# Sheet2.net
KiCad netlist of a schematic drawn in Altium Designer
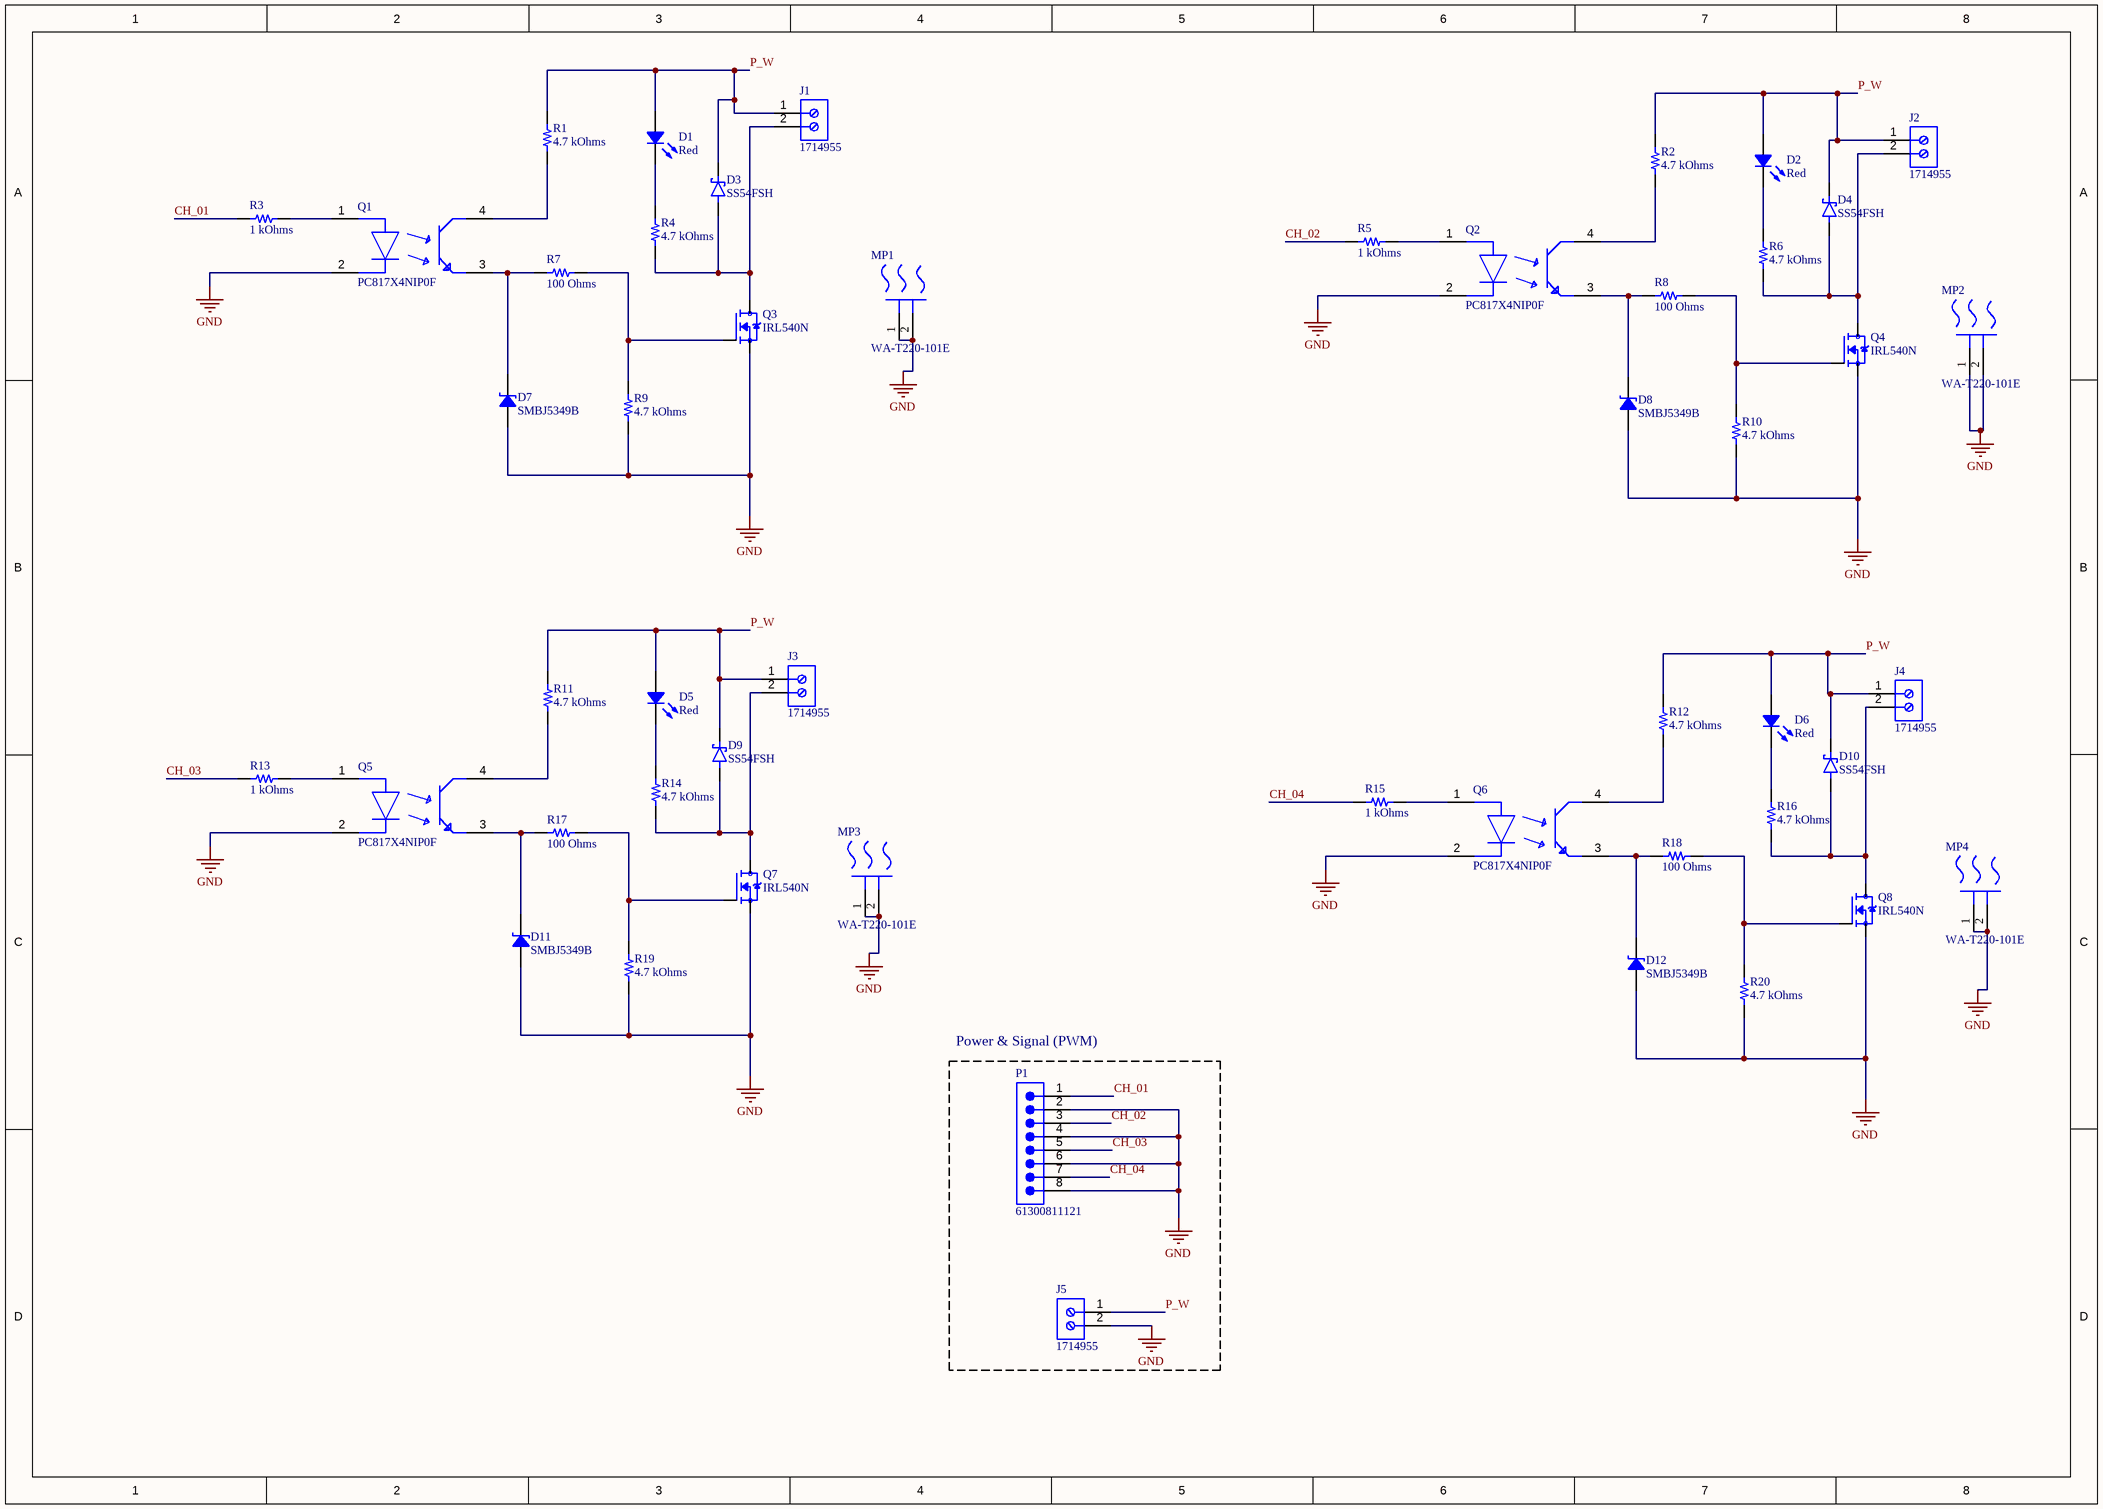
[diagram p0: Sheet2.SchDoc]

(export (version "E")
  (design (tool "Eeschema 10.0.6"))
  (components
    (comp (ref "D1")
      (value "Red")
      (footprint "LED 0603_1608 RED")
      (description "LED RED 0603 SMD")
      (fields (field (name "PART NUMBER") "5973005507F") (field (name "MANUFACTURER") "Dialight"))
      (libsource (lib "Celestial Altium Library - altium_library") (part "LED"))
    )
    (comp (ref "D2")
      (value "Red")
      (footprint "LED 0603_1608 RED")
      (description "LED RED 0603 SMD")
      (fields (field (name "PART NUMBER") "5973005507F") (field (name "MANUFACTURER") "Dialight"))
      (libsource (lib "Celestial Altium Library - altium_library") (part "LED"))
    )
    (comp (ref "D3")
      (value "SS54FSH")
      (footprint "SODFL4725X110N")
      (description "5A, 40V, Schottky Rectifier")
      (fields (field (name "MF") "Taiwan Semiconductor"))
      (libsource (lib "SS54FSH") (part "SS54FSH"))
    )
    (comp (ref "D4")
      (value "SS54FSH")
      (footprint "SODFL4725X110N")
      (description "5A, 40V, Schottky Rectifier")
      (fields (field (name "MF") "Taiwan Semiconductor"))
      (libsource (lib "SS54FSH") (part "SS54FSH"))
    )
    (comp (ref "D5")
      (value "Red")
      (footprint "LED 0603_1608 RED")
      (description "LED RED 0603 SMD")
      (fields (field (name "PART NUMBER") "5973005507F") (field (name "MANUFACTURER") "Dialight"))
      (libsource (lib "Celestial Altium Library - altium_library") (part "LED"))
    )
    (comp (ref "D6")
      (value "Red")
      (footprint "LED 0603_1608 RED")
      (description "LED RED 0603 SMD")
      (fields (field (name "PART NUMBER") "5973005507F") (field (name "MANUFACTURER") "Dialight"))
      (libsource (lib "Celestial Altium Library - altium_library") (part "LED"))
    )
    (comp (ref "D7")
      (value "SMBJ5349B")
      (footprint "DO214AA SMB")
      (description "DIODE ZENER 12V 5W DO214AA")
      (fields (field (name "PART NUMBER") "SMBJ5349B-TP") (field (name "MANUFACTURER") "Micro Commercial Co"))
      (libsource (lib "Celestial Altium Library - altium_library") (part "Diode Zener"))
    )
    (comp (ref "D8")
      (value "SMBJ5349B")
      (footprint "DO214AA SMB")
      (description "DIODE ZENER 12V 5W DO214AA")
      (fields (field (name "PART NUMBER") "SMBJ5349B-TP") (field (name "MANUFACTURER") "Micro Commercial Co"))
      (libsource (lib "Celestial Altium Library - altium_library") (part "Diode Zener"))
    )
    (comp (ref "D9")
      (value "SS54FSH")
      (footprint "SODFL4725X110N")
      (description "5A, 40V, Schottky Rectifier")
      (fields (field (name "MF") "Taiwan Semiconductor"))
      (libsource (lib "SS54FSH") (part "SS54FSH"))
    )
    (comp (ref "D10")
      (value "SS54FSH")
      (footprint "SODFL4725X110N")
      (description "5A, 40V, Schottky Rectifier")
      (fields (field (name "MF") "Taiwan Semiconductor"))
      (libsource (lib "SS54FSH") (part "SS54FSH"))
    )
    (comp (ref "D11")
      (value "SMBJ5349B")
      (footprint "DO214AA SMB")
      (description "DIODE ZENER 12V 5W DO214AA")
      (fields (field (name "PART NUMBER") "SMBJ5349B-TP") (field (name "MANUFACTURER") "Micro Commercial Co"))
      (libsource (lib "Celestial Altium Library - altium_library") (part "Diode Zener"))
    )
    (comp (ref "D12")
      (value "SMBJ5349B")
      (footprint "DO214AA SMB")
      (description "DIODE ZENER 12V 5W DO214AA")
      (fields (field (name "PART NUMBER") "SMBJ5349B-TP") (field (name "MANUFACTURER") "Micro Commercial Co"))
      (libsource (lib "Celestial Altium Library - altium_library") (part "Diode Zener"))
    )
    (comp (ref "J1")
      (value "1714955")
      (footprint "PHOE-1714955_V")
      (description "PC Terminal Block, Pitch 6.35 mm, 1 x 2 Position, Height 21.5 mm, Tail Lenght 5.1 mm, RoHS, Bulk")
      (fields (field (name "MANUFACTURER") "Phoenix Contact"))
      (libsource (lib "Altium Content Vault") (part "CN-1P-F-TB2"))
    )
    (comp (ref "J2")
      (value "1714955")
      (footprint "PHOE-1714955_V")
      (description "PC Terminal Block, Pitch 6.35 mm, 1 x 2 Position, Height 21.5 mm, Tail Lenght 5.1 mm, RoHS, Bulk")
      (fields (field (name "MANUFACTURER") "Phoenix Contact"))
      (libsource (lib "Altium Content Vault") (part "CN-1P-F-TB2"))
    )
    (comp (ref "J3")
      (value "1714955")
      (footprint "PHOE-1714955_V")
      (description "PC Terminal Block, Pitch 6.35 mm, 1 x 2 Position, Height 21.5 mm, Tail Lenght 5.1 mm, RoHS, Bulk")
      (fields (field (name "MANUFACTURER") "Phoenix Contact"))
      (libsource (lib "Altium Content Vault") (part "CN-1P-F-TB2"))
    )
    (comp (ref "J4")
      (value "1714955")
      (footprint "PHOE-1714955_V")
      (description "PC Terminal Block, Pitch 6.35 mm, 1 x 2 Position, Height 21.5 mm, Tail Lenght 5.1 mm, RoHS, Bulk")
      (fields (field (name "MANUFACTURER") "Phoenix Contact"))
      (libsource (lib "Altium Content Vault") (part "CN-1P-F-TB2"))
    )
    (comp (ref "J5")
      (value "1714955")
      (footprint "PHOE-1714955_V")
      (description "PC Terminal Block, Pitch 6.35 mm, 1 x 2 Position, Height 21.5 mm, Tail Lenght 5.1 mm, RoHS, Bulk")
      (fields (field (name "MANUFACTURER") "Phoenix Contact"))
      (libsource (lib "Altium Content Vault") (part "CN-1P-F-TB2"))
    )
    (comp (ref "MP1")
      (value "WA-T220-101E")
      (footprint "FP-WA-T220-101E-MFG")
      (description "HEATSINK AND CLIP FOR TO-220 BLK")
      (libsource (lib "Altium Content Vault") (part "1c0b9ce64b05bcdbb02c4237765ddae"))
    )
    (comp (ref "MP2")
      (value "WA-T220-101E")
      (footprint "FP-WA-T220-101E-MFG")
      (description "HEATSINK AND CLIP FOR TO-220 BLK")
      (libsource (lib "Altium Content Vault") (part "1c0b9ce64b05bcdbb02c4237765ddae"))
    )
    (comp (ref "MP3")
      (value "WA-T220-101E")
      (footprint "FP-WA-T220-101E-MFG")
      (description "HEATSINK AND CLIP FOR TO-220 BLK")
      (libsource (lib "Altium Content Vault") (part "1c0b9ce64b05bcdbb02c4237765ddae"))
    )
    (comp (ref "MP4")
      (value "WA-T220-101E")
      (footprint "FP-WA-T220-101E-MFG")
      (description "HEATSINK AND CLIP FOR TO-220 BLK")
      (libsource (lib "Altium Content Vault") (part "1c0b9ce64b05bcdbb02c4237765ddae"))
    )
    (comp (ref "P1")
      (value "61300811121")
      (footprint "61300811121")
      (libsource (lib "Altium Content Vault") (part "Header_Male_1R_08P"))
    )
    (comp (ref "Q1")
      (value "PC817X4NIP0F")
      (footprint "FP-PC817X4NIP0F-MFG")
      (description "OPTOISOLATOR 5KV TRANS 4SMD")
      (fields
        (field (name "OCTOPART") "https://octopart.com/pc817x4nip0f-sharp-20650453")
        (field (name "MANUFACTURER") "Sharp")
      )
      (libsource (lib "Altium Content Vault") (part "8ff5844b63c0dea0057760e9ee25456"))
    )
    (comp (ref "Q2")
      (value "PC817X4NIP0F")
      (footprint "FP-PC817X4NIP0F-MFG")
      (description "OPTOISOLATOR 5KV TRANS 4SMD")
      (fields
        (field (name "OCTOPART") "https://octopart.com/pc817x4nip0f-sharp-20650453")
        (field (name "MANUFACTURER") "Sharp")
      )
      (libsource (lib "Altium Content Vault") (part "8ff5844b63c0dea0057760e9ee25456"))
    )
    (comp (ref "Q3")
      (value "IRL540N")
      (footprint "TO254P1054X469X1930-3")
      (fields (field (name "MP") "IRF540NPBF") (field (name "MF") "Infineon"))
      (libsource (lib "IRF540NPBF") (part "IRF540NPBF"))
    )
    (comp (ref "Q4")
      (value "IRL540N")
      (footprint "TO254P1054X469X1930-3")
      (fields (field (name "MP") "IRF540NPBF") (field (name "MF") "Infineon"))
      (libsource (lib "IRF540NPBF") (part "IRF540NPBF"))
    )
    (comp (ref "Q5")
      (value "PC817X4NIP0F")
      (footprint "FP-PC817X4NIP0F-MFG")
      (description "OPTOISOLATOR 5KV TRANS 4SMD")
      (fields
        (field (name "OCTOPART") "https://octopart.com/pc817x4nip0f-sharp-20650453")
        (field (name "MANUFACTURER") "Sharp")
      )
      (libsource (lib "Altium Content Vault") (part "8ff5844b63c0dea0057760e9ee25456"))
    )
    (comp (ref "Q6")
      (value "PC817X4NIP0F")
      (footprint "FP-PC817X4NIP0F-MFG")
      (description "OPTOISOLATOR 5KV TRANS 4SMD")
      (fields
        (field (name "OCTOPART") "https://octopart.com/pc817x4nip0f-sharp-20650453")
        (field (name "MANUFACTURER") "Sharp")
      )
      (libsource (lib "Altium Content Vault") (part "8ff5844b63c0dea0057760e9ee25456"))
    )
    (comp (ref "Q7")
      (value "IRL540N")
      (footprint "TO254P1054X469X1930-3")
      (fields (field (name "MP") "IRF540NPBF") (field (name "MF") "Infineon"))
      (libsource (lib "IRF540NPBF") (part "IRF540NPBF"))
    )
    (comp (ref "Q8")
      (value "IRL540N")
      (footprint "TO254P1054X469X1930-3")
      (fields (field (name "MP") "IRF540NPBF") (field (name "MF") "Infineon"))
      (libsource (lib "IRF540NPBF") (part "IRF540NPBF"))
    )
    (comp (ref "R1")
      (value "4.7 kOhms")
      (footprint "RES 0603_1608")
      (description "RES SMD 4.7K OHM 0.1% 1/10W 0603")
      (fields
        (field (name "PART NUMBER") "ERA-3AEB472V")
        (field (name "MANUFACTURER") "Panasonic Electronic Components")
      )
      (libsource (lib "Celestial Altium Library - altium_library") (part "Resistor"))
    )
    (comp (ref "R2")
      (value "4.7 kOhms")
      (footprint "RES 0603_1608")
      (description "RES SMD 4.7K OHM 0.1% 1/10W 0603")
      (fields
        (field (name "PART NUMBER") "ERA-3AEB472V")
        (field (name "MANUFACTURER") "Panasonic Electronic Components")
      )
      (libsource (lib "Celestial Altium Library - altium_library") (part "Resistor"))
    )
    (comp (ref "R3")
      (value "1 kOhms")
      (footprint "RES 0603_1608")
      (description "RES SMD 1K OHM 0.1% 1/16W 0603")
      (fields
        (field (name "PART NUMBER") "CPF0603B1K0E")
        (field (name "MANUFACTURER") "TE Connectivity Passive Product")
      )
      (libsource (lib "Celestial Altium Library - altium_library") (part "Resistor"))
    )
    (comp (ref "R4")
      (value "4.7 kOhms")
      (footprint "RES 0603_1608")
      (description "RES SMD 4.7K OHM 0.1% 1/10W 0603")
      (fields
        (field (name "PART NUMBER") "ERA-3AEB472V")
        (field (name "MANUFACTURER") "Panasonic Electronic Components")
      )
      (libsource (lib "Celestial Altium Library - altium_library") (part "Resistor"))
    )
    (comp (ref "R5")
      (value "1 kOhms")
      (footprint "RES 0603_1608")
      (description "RES SMD 1K OHM 0.1% 1/16W 0603")
      (fields
        (field (name "PART NUMBER") "CPF0603B1K0E")
        (field (name "MANUFACTURER") "TE Connectivity Passive Product")
      )
      (libsource (lib "Celestial Altium Library - altium_library") (part "Resistor"))
    )
    (comp (ref "R6")
      (value "4.7 kOhms")
      (footprint "RES 0603_1608")
      (description "RES SMD 4.7K OHM 0.1% 1/10W 0603")
      (fields
        (field (name "PART NUMBER") "ERA-3AEB472V")
        (field (name "MANUFACTURER") "Panasonic Electronic Components")
      )
      (libsource (lib "Celestial Altium Library - altium_library") (part "Resistor"))
    )
    (comp (ref "R7")
      (value "100 Ohms")
      (footprint "RES 0603_1608")
      (description "RES 100 OHM 0.1% 1/16W 0603")
      (fields
        (field (name "PART NUMBER") "RNCS0603BKE100R")
        (field (name "MANUFACTURER") "Stackpole Electronics Inc")
      )
      (libsource (lib "Celestial Altium Library - altium_library") (part "Resistor"))
    )
    (comp (ref "R8")
      (value "100 Ohms")
      (footprint "RES 0603_1608")
      (description "RES 100 OHM 0.1% 1/16W 0603")
      (fields
        (field (name "PART NUMBER") "RNCS0603BKE100R")
        (field (name "MANUFACTURER") "Stackpole Electronics Inc")
      )
      (libsource (lib "Celestial Altium Library - altium_library") (part "Resistor"))
    )
    (comp (ref "R9")
      (value "4.7 kOhms")
      (footprint "RES 0603_1608")
      (description "RES SMD 4.7K OHM 0.1% 1/10W 0603")
      (fields
        (field (name "PART NUMBER") "ERA-3AEB472V")
        (field (name "MANUFACTURER") "Panasonic Electronic Components")
      )
      (libsource (lib "Celestial Altium Library - altium_library") (part "Resistor"))
    )
    (comp (ref "R10")
      (value "4.7 kOhms")
      (footprint "RES 0603_1608")
      (description "RES SMD 4.7K OHM 0.1% 1/10W 0603")
      (fields
        (field (name "PART NUMBER") "ERA-3AEB472V")
        (field (name "MANUFACTURER") "Panasonic Electronic Components")
      )
      (libsource (lib "Celestial Altium Library - altium_library") (part "Resistor"))
    )
    (comp (ref "R11")
      (value "4.7 kOhms")
      (footprint "RES 0603_1608")
      (description "RES SMD 4.7K OHM 0.1% 1/10W 0603")
      (fields
        (field (name "PART NUMBER") "ERA-3AEB472V")
        (field (name "MANUFACTURER") "Panasonic Electronic Components")
      )
      (libsource (lib "Celestial Altium Library - altium_library") (part "Resistor"))
    )
    (comp (ref "R12")
      (value "4.7 kOhms")
      (footprint "RES 0603_1608")
      (description "RES SMD 4.7K OHM 0.1% 1/10W 0603")
      (fields
        (field (name "PART NUMBER") "ERA-3AEB472V")
        (field (name "MANUFACTURER") "Panasonic Electronic Components")
      )
      (libsource (lib "Celestial Altium Library - altium_library") (part "Resistor"))
    )
    (comp (ref "R13")
      (value "1 kOhms")
      (footprint "RES 0603_1608")
      (description "RES SMD 1K OHM 0.1% 1/16W 0603")
      (fields
        (field (name "PART NUMBER") "CPF0603B1K0E")
        (field (name "MANUFACTURER") "TE Connectivity Passive Product")
      )
      (libsource (lib "Celestial Altium Library - altium_library") (part "Resistor"))
    )
    (comp (ref "R14")
      (value "4.7 kOhms")
      (footprint "RES 0603_1608")
      (description "RES SMD 4.7K OHM 0.1% 1/10W 0603")
      (fields
        (field (name "PART NUMBER") "ERA-3AEB472V")
        (field (name "MANUFACTURER") "Panasonic Electronic Components")
      )
      (libsource (lib "Celestial Altium Library - altium_library") (part "Resistor"))
    )
    (comp (ref "R15")
      (value "1 kOhms")
      (footprint "RES 0603_1608")
      (description "RES SMD 1K OHM 0.1% 1/16W 0603")
      (fields
        (field (name "PART NUMBER") "CPF0603B1K0E")
        (field (name "MANUFACTURER") "TE Connectivity Passive Product")
      )
      (libsource (lib "Celestial Altium Library - altium_library") (part "Resistor"))
    )
    (comp (ref "R16")
      (value "4.7 kOhms")
      (footprint "RES 0603_1608")
      (description "RES SMD 4.7K OHM 0.1% 1/10W 0603")
      (fields
        (field (name "PART NUMBER") "ERA-3AEB472V")
        (field (name "MANUFACTURER") "Panasonic Electronic Components")
      )
      (libsource (lib "Celestial Altium Library - altium_library") (part "Resistor"))
    )
    (comp (ref "R17")
      (value "100 Ohms")
      (footprint "RES 0603_1608")
      (description "RES 100 OHM 0.1% 1/16W 0603")
      (fields
        (field (name "PART NUMBER") "RNCS0603BKE100R")
        (field (name "MANUFACTURER") "Stackpole Electronics Inc")
      )
      (libsource (lib "Celestial Altium Library - altium_library") (part "Resistor"))
    )
    (comp (ref "R18")
      (value "100 Ohms")
      (footprint "RES 0603_1608")
      (description "RES 100 OHM 0.1% 1/16W 0603")
      (fields
        (field (name "PART NUMBER") "RNCS0603BKE100R")
        (field (name "MANUFACTURER") "Stackpole Electronics Inc")
      )
      (libsource (lib "Celestial Altium Library - altium_library") (part "Resistor"))
    )
    (comp (ref "R19")
      (value "4.7 kOhms")
      (footprint "RES 0603_1608")
      (description "RES SMD 4.7K OHM 0.1% 1/10W 0603")
      (fields
        (field (name "PART NUMBER") "ERA-3AEB472V")
        (field (name "MANUFACTURER") "Panasonic Electronic Components")
      )
      (libsource (lib "Celestial Altium Library - altium_library") (part "Resistor"))
    )
    (comp (ref "R20")
      (value "4.7 kOhms")
      (footprint "RES 0603_1608")
      (description "RES SMD 4.7K OHM 0.1% 1/10W 0603")
      (fields
        (field (name "PART NUMBER") "ERA-3AEB472V")
        (field (name "MANUFACTURER") "Panasonic Electronic Components")
      )
      (libsource (lib "Celestial Altium Library - altium_library") (part "Resistor"))
    )
  )
  (nets
    (net (code "1") (name "/CH_01") (class "Default")
      (node (ref "P1") (pin "1") (pinfunction "1_1") (pintype "passive"))
      (node (ref "R3") (pin "1") (pinfunction "1_1") (pintype "passive"))
    )
    (net (code "2") (name "/CH_02") (class "Default")
      (node (ref "P1") (pin "3") (pinfunction "3_3") (pintype "passive"))
      (node (ref "R5") (pin "1") (pinfunction "1_1") (pintype "passive"))
    )
    (net (code "3") (name "/CH_03") (class "Default")
      (node (ref "P1") (pin "5") (pinfunction "5_5") (pintype "passive"))
      (node (ref "R13") (pin "1") (pinfunction "1_1") (pintype "passive"))
    )
    (net (code "4") (name "/CH_04") (class "Default")
      (node (ref "P1") (pin "7") (pinfunction "7_7") (pintype "passive"))
      (node (ref "R15") (pin "1") (pinfunction "1_1") (pintype "passive"))
    )
    (net (code "5") (name "/P_W") (class "Default")
      (node (ref "D1") (pin "1") (pinfunction "1_1") (pintype "passive"))
      (node (ref "D10") (pin "C") (pinfunction "K_C") (pintype "passive"))
      (node (ref "D2") (pin "1") (pinfunction "1_1") (pintype "passive"))
      (node (ref "D3") (pin "C") (pinfunction "K_C") (pintype "passive"))
      (node (ref "D4") (pin "C") (pinfunction "K_C") (pintype "passive"))
      (node (ref "D5") (pin "1") (pinfunction "1_1") (pintype "passive"))
      (node (ref "D6") (pin "1") (pinfunction "1_1") (pintype "passive"))
      (node (ref "D9") (pin "C") (pinfunction "K_C") (pintype "passive"))
      (node (ref "J1") (pin "1") (pinfunction "1_1") (pintype "passive"))
      (node (ref "J2") (pin "1") (pinfunction "1_1") (pintype "passive"))
      (node (ref "J3") (pin "1") (pinfunction "1_1") (pintype "passive"))
      (node (ref "J4") (pin "1") (pinfunction "1_1") (pintype "passive"))
      (node (ref "J5") (pin "1") (pinfunction "1_1") (pintype "passive"))
      (node (ref "R1") (pin "2") (pinfunction "2_2") (pintype "passive"))
      (node (ref "R11") (pin "2") (pinfunction "2_2") (pintype "passive"))
      (node (ref "R12") (pin "2") (pinfunction "2_2") (pintype "passive"))
      (node (ref "R2") (pin "2") (pinfunction "2_2") (pintype "passive"))
    )
    (net (code "6") (name "GND") (class "Default")
      (node (ref "D11") (pin "1") (pinfunction "1_1") (pintype "passive"))
      (node (ref "D12") (pin "1") (pinfunction "1_1") (pintype "passive"))
      (node (ref "D7") (pin "1") (pinfunction "1_1") (pintype "passive"))
      (node (ref "D8") (pin "1") (pinfunction "1_1") (pintype "passive"))
      (node (ref "J5") (pin "2") (pinfunction "2_2") (pintype "passive"))
      (node (ref "MP1") (pin "1") (pinfunction "MNT_1_1") (pintype "passive"))
      (node (ref "MP1") (pin "2") (pinfunction "MNT_2_2") (pintype "passive"))
      (node (ref "MP2") (pin "1") (pinfunction "MNT_1_1") (pintype "passive"))
      (node (ref "MP2") (pin "2") (pinfunction "MNT_2_2") (pintype "passive"))
      (node (ref "MP3") (pin "1") (pinfunction "MNT_1_1") (pintype "passive"))
      (node (ref "MP3") (pin "2") (pinfunction "MNT_2_2") (pintype "passive"))
      (node (ref "MP4") (pin "1") (pinfunction "MNT_1_1") (pintype "passive"))
      (node (ref "MP4") (pin "2") (pinfunction "MNT_2_2") (pintype "passive"))
      (node (ref "P1") (pin "2") (pinfunction "2_2") (pintype "passive"))
      (node (ref "P1") (pin "4") (pinfunction "4_4") (pintype "passive"))
      (node (ref "P1") (pin "6") (pinfunction "6_6") (pintype "passive"))
      (node (ref "P1") (pin "8") (pinfunction "8_8") (pintype "passive"))
      (node (ref "Q1") (pin "2") (pinfunction "C_2") (pintype "passive"))
      (node (ref "Q2") (pin "2") (pinfunction "C_2") (pintype "passive"))
      (node (ref "Q3") (pin "3") (pinfunction "S_3") (pintype "passive"))
      (node (ref "Q4") (pin "3") (pinfunction "S_3") (pintype "passive"))
      (node (ref "Q5") (pin "2") (pinfunction "C_2") (pintype "passive"))
      (node (ref "Q6") (pin "2") (pinfunction "C_2") (pintype "passive"))
      (node (ref "Q7") (pin "3") (pinfunction "S_3") (pintype "passive"))
      (node (ref "Q8") (pin "3") (pinfunction "S_3") (pintype "passive"))
      (node (ref "R10") (pin "1") (pinfunction "1_1") (pintype "passive"))
      (node (ref "R19") (pin "1") (pinfunction "1_1") (pintype "passive"))
      (node (ref "R20") (pin "1") (pinfunction "1_1") (pintype "passive"))
      (node (ref "R9") (pin "1") (pinfunction "1_1") (pintype "passive"))
    )
    (net (code "7") (name "Net-(D1-Pad2)") (class "Default")
      (node (ref "D1") (pin "2") (pinfunction "2_2") (pintype "passive"))
      (node (ref "R4") (pin "2") (pinfunction "2_2") (pintype "passive"))
    )
    (net (code "8") (name "Net-(D2-Pad2)") (class "Default")
      (node (ref "D2") (pin "2") (pinfunction "2_2") (pintype "passive"))
      (node (ref "R6") (pin "2") (pinfunction "2_2") (pintype "passive"))
    )
    (net (code "9") (name "Net-(D5-Pad2)") (class "Default")
      (node (ref "D5") (pin "2") (pinfunction "2_2") (pintype "passive"))
      (node (ref "R14") (pin "2") (pinfunction "2_2") (pintype "passive"))
    )
    (net (code "10") (name "Net-(D6-Pad2)") (class "Default")
      (node (ref "D6") (pin "2") (pinfunction "2_2") (pintype "passive"))
      (node (ref "R16") (pin "2") (pinfunction "2_2") (pintype "passive"))
    )
    (net (code "11") (name "Net-(Q1-A)") (class "Default")
      (node (ref "Q1") (pin "1") (pinfunction "A_1") (pintype "passive"))
      (node (ref "R3") (pin "2") (pinfunction "2_2") (pintype "passive"))
    )
    (net (code "12") (name "Net-(Q1-C-Pad4)") (class "Default")
      (node (ref "Q1") (pin "4") (pinfunction "C_4") (pintype "passive"))
      (node (ref "R1") (pin "1") (pinfunction "1_1") (pintype "passive"))
    )
    (net (code "13") (name "Net-(Q1-E)") (class "Default")
      (node (ref "D7") (pin "2") (pinfunction "2_2") (pintype "passive"))
      (node (ref "Q1") (pin "3") (pinfunction "E_3") (pintype "passive"))
      (node (ref "R7") (pin "1") (pinfunction "1_1") (pintype "passive"))
    )
    (net (code "14") (name "Net-(Q2-A)") (class "Default")
      (node (ref "Q2") (pin "1") (pinfunction "A_1") (pintype "passive"))
      (node (ref "R5") (pin "2") (pinfunction "2_2") (pintype "passive"))
    )
    (net (code "15") (name "Net-(Q2-C-Pad4)") (class "Default")
      (node (ref "Q2") (pin "4") (pinfunction "C_4") (pintype "passive"))
      (node (ref "R2") (pin "1") (pinfunction "1_1") (pintype "passive"))
    )
    (net (code "16") (name "Net-(Q2-E)") (class "Default")
      (node (ref "D8") (pin "2") (pinfunction "2_2") (pintype "passive"))
      (node (ref "Q2") (pin "3") (pinfunction "E_3") (pintype "passive"))
      (node (ref "R8") (pin "1") (pinfunction "1_1") (pintype "passive"))
    )
    (net (code "17") (name "Net-(Q3-D)") (class "Default")
      (node (ref "D3") (pin "A") (pinfunction "A_A") (pintype "passive"))
      (node (ref "J1") (pin "2") (pinfunction "2_2") (pintype "passive"))
      (node (ref "Q3") (pin "2") (pinfunction "D_2") (pintype "passive"))
      (node (ref "R4") (pin "1") (pinfunction "1_1") (pintype "passive"))
    )
    (net (code "18") (name "Net-(Q3-G)") (class "Default")
      (node (ref "Q3") (pin "1") (pinfunction "G_1") (pintype "passive"))
      (node (ref "R7") (pin "2") (pinfunction "2_2") (pintype "passive"))
      (node (ref "R9") (pin "2") (pinfunction "2_2") (pintype "passive"))
    )
    (net (code "19") (name "Net-(Q4-D)") (class "Default")
      (node (ref "D4") (pin "A") (pinfunction "A_A") (pintype "passive"))
      (node (ref "J2") (pin "2") (pinfunction "2_2") (pintype "passive"))
      (node (ref "Q4") (pin "2") (pinfunction "D_2") (pintype "passive"))
      (node (ref "R6") (pin "1") (pinfunction "1_1") (pintype "passive"))
    )
    (net (code "20") (name "Net-(Q4-G)") (class "Default")
      (node (ref "Q4") (pin "1") (pinfunction "G_1") (pintype "passive"))
      (node (ref "R10") (pin "2") (pinfunction "2_2") (pintype "passive"))
      (node (ref "R8") (pin "2") (pinfunction "2_2") (pintype "passive"))
    )
    (net (code "21") (name "Net-(Q5-A)") (class "Default")
      (node (ref "Q5") (pin "1") (pinfunction "A_1") (pintype "passive"))
      (node (ref "R13") (pin "2") (pinfunction "2_2") (pintype "passive"))
    )
    (net (code "22") (name "Net-(Q5-C-Pad4)") (class "Default")
      (node (ref "Q5") (pin "4") (pinfunction "C_4") (pintype "passive"))
      (node (ref "R11") (pin "1") (pinfunction "1_1") (pintype "passive"))
    )
    (net (code "23") (name "Net-(Q5-E)") (class "Default")
      (node (ref "D11") (pin "2") (pinfunction "2_2") (pintype "passive"))
      (node (ref "Q5") (pin "3") (pinfunction "E_3") (pintype "passive"))
      (node (ref "R17") (pin "1") (pinfunction "1_1") (pintype "passive"))
    )
    (net (code "24") (name "Net-(Q6-A)") (class "Default")
      (node (ref "Q6") (pin "1") (pinfunction "A_1") (pintype "passive"))
      (node (ref "R15") (pin "2") (pinfunction "2_2") (pintype "passive"))
    )
    (net (code "25") (name "Net-(Q6-C-Pad4)") (class "Default")
      (node (ref "Q6") (pin "4") (pinfunction "C_4") (pintype "passive"))
      (node (ref "R12") (pin "1") (pinfunction "1_1") (pintype "passive"))
    )
    (net (code "26") (name "Net-(Q6-E)") (class "Default")
      (node (ref "D12") (pin "2") (pinfunction "2_2") (pintype "passive"))
      (node (ref "Q6") (pin "3") (pinfunction "E_3") (pintype "passive"))
      (node (ref "R18") (pin "1") (pinfunction "1_1") (pintype "passive"))
    )
    (net (code "27") (name "Net-(Q7-D)") (class "Default")
      (node (ref "D9") (pin "A") (pinfunction "A_A") (pintype "passive"))
      (node (ref "J3") (pin "2") (pinfunction "2_2") (pintype "passive"))
      (node (ref "Q7") (pin "2") (pinfunction "D_2") (pintype "passive"))
      (node (ref "R14") (pin "1") (pinfunction "1_1") (pintype "passive"))
    )
    (net (code "28") (name "Net-(Q7-G)") (class "Default")
      (node (ref "Q7") (pin "1") (pinfunction "G_1") (pintype "passive"))
      (node (ref "R17") (pin "2") (pinfunction "2_2") (pintype "passive"))
      (node (ref "R19") (pin "2") (pinfunction "2_2") (pintype "passive"))
    )
    (net (code "29") (name "Net-(Q8-D)") (class "Default")
      (node (ref "D10") (pin "A") (pinfunction "A_A") (pintype "passive"))
      (node (ref "J4") (pin "2") (pinfunction "2_2") (pintype "passive"))
      (node (ref "Q8") (pin "2") (pinfunction "D_2") (pintype "passive"))
      (node (ref "R16") (pin "1") (pinfunction "1_1") (pintype "passive"))
    )
    (net (code "30") (name "Net-(Q8-G)") (class "Default")
      (node (ref "Q8") (pin "1") (pinfunction "G_1") (pintype "passive"))
      (node (ref "R18") (pin "2") (pinfunction "2_2") (pintype "passive"))
      (node (ref "R20") (pin "2") (pinfunction "2_2") (pintype "passive"))
    )
  )
)
